# Microcontroller.net
KiCad netlist of a schematic drawn in Altium Designer
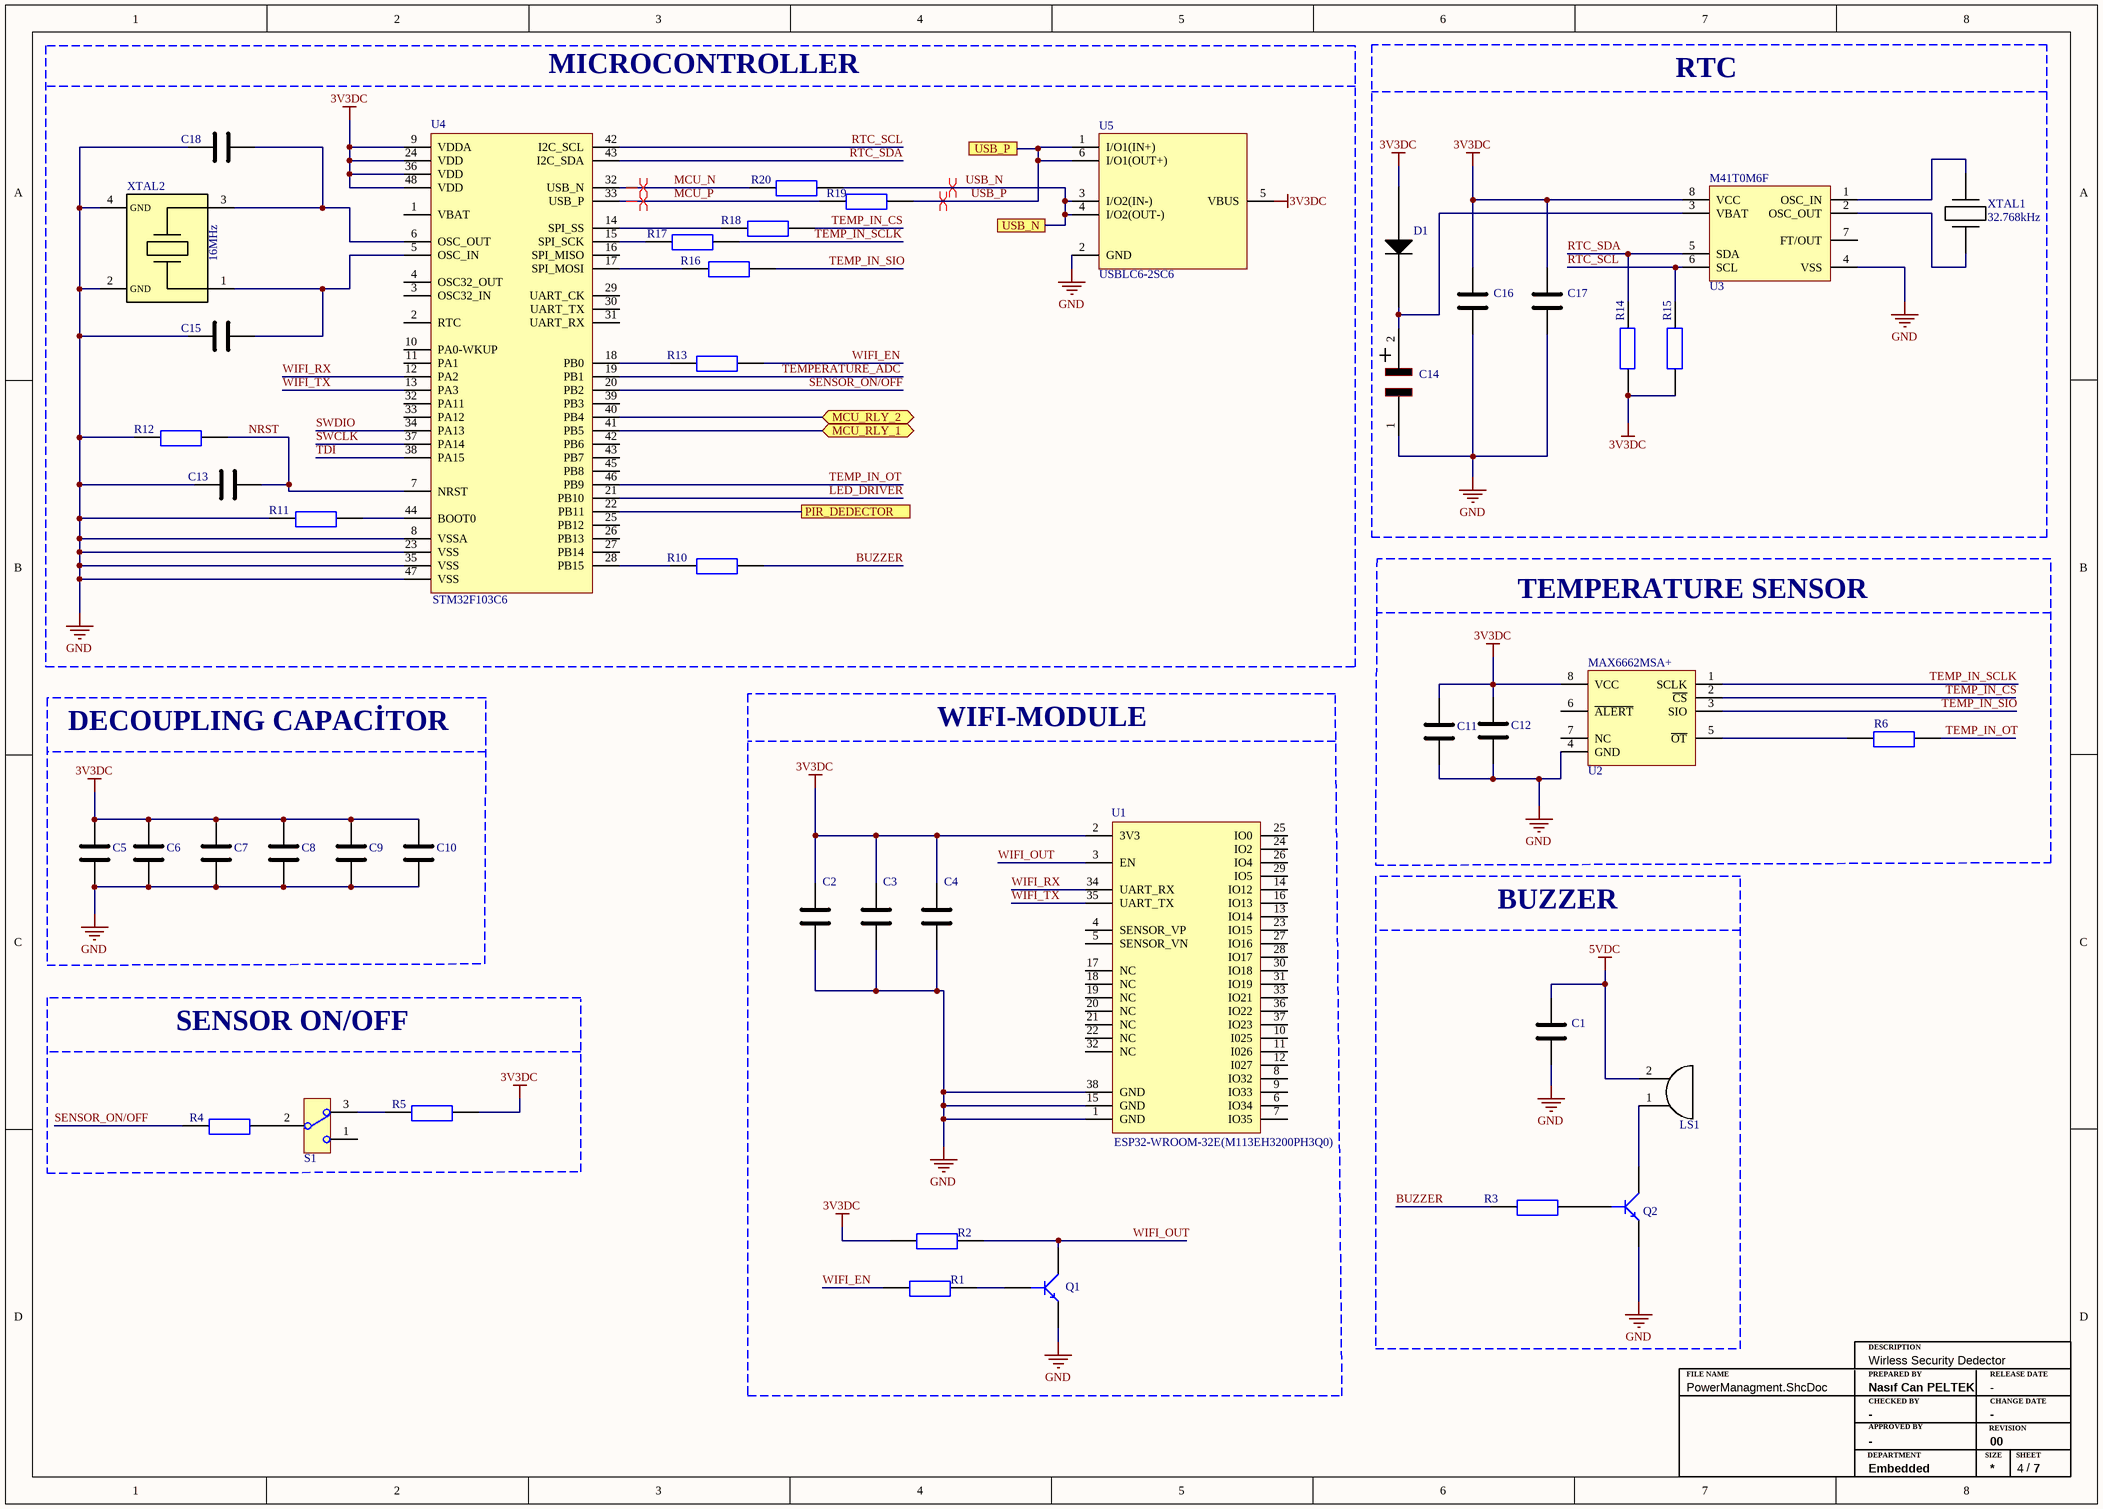
[diagram p0: Microcontroller.SchDoc]

(export (version "E")
  (design (tool "Eeschema 10.0.6"))
  (components
    (comp (ref "C1")
      (value "C0603C104K5RAC7867")
      (footprint "CAP_603")
      (description "CAP CER 100nF 50V 10% SMD 0603")
      (fields
        (field (name "MANUFACTURER") "KEMET")
        (field (name "MANUFACTURER PART NUMBER") "C0603C104K5RACTU")
        (field (name "DESIGNED BY") "Nasıf Can Peltek")
      )
      (libsource (lib "OV_00_Library") (part "CAP CER 100nF 0603"))
    )
    (comp (ref "C2")
      (value "CL21A475KAQNNNE")
      (footprint "CAP_805")
      (description "CAP CER 4.7UF 25V 10% 0805")
      (fields
        (field (name "MANUFACTURER") "Samsung")
        (field (name "TOLERANCE") "10%")
        (field (name "DESIGNED BY") "Nasıf Can Peltek")
      )
      (libsource (lib "OV_00_Library") (part "CAP CER 4.7uF 0805"))
    )
    (comp (ref "C3")
      (value "CL21B105KBFNNNE")
      (footprint "CAP_805")
      (description "CAP CER 1UF 50V 10% 0805")
      (fields
        (field (name "MANUFACTURER") "Samsung")
        (field (name "TOLERANCE") "10%")
        (field (name "DESIGNED BY") "Nasıf Can Peltek")
      )
      (libsource (lib "OV_00_Library") (part "CAP CER 1uF 0805"))
    )
    (comp (ref "C4")
      (value "C0603C104K5RAC7867")
      (footprint "CAP_603")
      (description "CAP CER 100nF 50V 10% SMD 0603")
      (fields
        (field (name "MANUFACTURER") "KEMET")
        (field (name "MANUFACTURER PART NUMBER") "C0603C104K5RACTU")
        (field (name "DESIGNED BY") "Nasıf Can Peltek")
      )
      (libsource (lib "OV_00_Library") (part "CAP CER 100nF 0603"))
    )
    (comp (ref "C5")
      (value "CL21B105KBFNNNE")
      (footprint "CAP_805")
      (description "CAP CER 1UF 50V 10% 0805")
      (fields
        (field (name "MANUFACTURER") "Samsung")
        (field (name "TOLERANCE") "10%")
        (field (name "DESIGNED BY") "Nasıf Can Peltek")
      )
      (libsource (lib "OV_00_Library") (part "CAP CER 1uF 0805"))
    )
    (comp (ref "C6")
      (value "CL21A475KAQNNNE")
      (footprint "CAP_805")
      (description "CAP CER 4.7UF 25V 10% 0805")
      (fields
        (field (name "MANUFACTURER") "Samsung")
        (field (name "TOLERANCE") "10%")
        (field (name "DESIGNED BY") "Nasıf Can Peltek")
      )
      (libsource (lib "OV_00_Library") (part "CAP CER 4.7uF 0805"))
    )
    (comp (ref "C7")
      (value "C0603C104K5RAC7867")
      (footprint "CAP_603")
      (description "CAP CER 100nF 50V 10% SMD 0603")
      (fields
        (field (name "MANUFACTURER") "KEMET")
        (field (name "MANUFACTURER PART NUMBER") "C0603C104K5RACTU")
        (field (name "DESIGNED BY") "Nasıf Can Peltek")
      )
      (libsource (lib "OV_00_Library") (part "CAP CER 100nF 0603"))
    )
    (comp (ref "C8")
      (value "C0603C104K5RAC7867")
      (footprint "CAP_603")
      (description "CAP CER 100nF 50V 10% SMD 0603")
      (fields
        (field (name "MANUFACTURER") "KEMET")
        (field (name "MANUFACTURER PART NUMBER") "C0603C104K5RACTU")
        (field (name "DESIGNED BY") "Nasıf Can Peltek")
      )
      (libsource (lib "OV_00_Library") (part "CAP CER 100nF 0603"))
    )
    (comp (ref "C9")
      (value "C0603C104K5RAC7867")
      (footprint "CAP_603")
      (description "CAP CER 100nF 50V 10% SMD 0603")
      (fields
        (field (name "MANUFACTURER") "KEMET")
        (field (name "MANUFACTURER PART NUMBER") "C0603C104K5RACTU")
        (field (name "DESIGNED BY") "Nasıf Can Peltek")
      )
      (libsource (lib "OV_00_Library") (part "CAP CER 100nF 0603"))
    )
    (comp (ref "C10")
      (value "C0603C104K5RAC7867")
      (footprint "CAP_603")
      (description "CAP CER 100nF 50V 10% SMD 0603")
      (fields
        (field (name "MANUFACTURER") "KEMET")
        (field (name "MANUFACTURER PART NUMBER") "C0603C104K5RACTU")
        (field (name "DESIGNED BY") "Nasıf Can Peltek")
      )
      (libsource (lib "OV_00_Library") (part "CAP CER 100nF 0603"))
    )
    (comp (ref "C11")
      (value "CL21B105KBFNNNE")
      (footprint "CAP_805")
      (description "CAP CER 1UF 50V 10% 0805")
      (fields
        (field (name "MANUFACTURER") "Samsung")
        (field (name "TOLERANCE") "10%")
        (field (name "DESIGNED BY") "Nasıf Can Peltek")
      )
      (libsource (lib "OV_00_Library") (part "CAP CER 1uF 0805"))
    )
    (comp (ref "C12")
      (value "C0603C104K5RAC7867")
      (footprint "CAP_603")
      (description "CAP CER 100nF 50V 10% SMD 0603")
      (fields
        (field (name "MANUFACTURER") "KEMET")
        (field (name "MANUFACTURER PART NUMBER") "C0603C104K5RACTU")
        (field (name "DESIGNED BY") "Nasıf Can Peltek")
      )
      (libsource (lib "OV_00_Library") (part "CAP CER 100nF 0603"))
    )
    (comp (ref "C13")
      (value "C0603C104K5RAC7867")
      (footprint "CAP_603")
      (description "CAP CER 100nF 50V 10% SMD 0603")
      (fields
        (field (name "MANUFACTURER") "KEMET")
        (field (name "MANUFACTURER PART NUMBER") "C0603C104K5RACTU")
        (field (name "DESIGNED BY") "Nasıf Can Peltek")
      )
      (libsource (lib "OV_00_Library") (part "CAP CER 100nF 0603"))
    )
    (comp (ref "C14")
      (value "ESH477M050AH4AA")
      (footprint "CAP_RADIAL_D10_P5")
      (description "Aluminum Electrolytic Capacitors Radial, Can  470 µF 50 V 2000 Hrs @ 105°C")
      (fields
        (field (name "MANUFACTURER") "KEMET")
        (field (name "TOLERANCE") "20%")
        (field (name "DESIGNED BY") "Nasıf Can Peltek")
      )
      (libsource (lib "OV_00_Library") (part "CAP ALU 470uF"))
    )
    (comp (ref "C15")
      (value "CL10C200JB8NNNC")
      (footprint "CAP_603")
      (description "CAP CER 20PF 50V 5% SMD 0603")
      (fields
        (field (name "MANUFACTURER") "Samsung")
        (field (name "TOLERANCE") "5%")
        (field (name "DESIGNED BY") "Nasıf Can Peltek")
      )
      (libsource (lib "OV_00_Library") (part "CAP CER 20pF 0603"))
    )
    (comp (ref "C16")
      (value "CL21B104KBCNNNC")
      (footprint "CAP_805")
      (description "CAP CER 0.1UF 50V 10%0805")
      (fields
        (field (name "MANUFACTURER") "Samsung")
        (field (name "TOLERANCE") "10%")
        (field (name "DESIGNED BY") "Nasıf Can Peltek")
      )
      (libsource (lib "OV_00_Library") (part "CAP CER 100nF 0805"))
    )
    (comp (ref "C17")
      (value "CL21B105KBFNNNE")
      (footprint "CAP_805")
      (description "CAP CER 1UF 50V 10% 0805")
      (fields
        (field (name "MANUFACTURER") "Samsung")
        (field (name "TOLERANCE") "10%")
        (field (name "DESIGNED BY") "Nasıf Can Peltek")
      )
      (libsource (lib "OV_00_Library") (part "CAP CER 1uF 0805"))
    )
    (comp (ref "C18")
      (value "CL10C200JB8NNNC")
      (footprint "CAP_603")
      (description "CAP CER 20PF 50V 5% SMD 0603")
      (fields
        (field (name "MANUFACTURER") "Samsung")
        (field (name "TOLERANCE") "5%")
        (field (name "DESIGNED BY") "Nasıf Can Peltek")
      )
      (libsource (lib "OV_00_Library") (part "CAP CER 20pF 0603"))
    )
    (comp (ref "D1")
      (value "1N4148WS")
      (footprint "SOD-323F")
      (description "Diode 75 V 150mA Surface Mount SOD-323F")
      (fields
        (field (name "MANUFACTURER") "ON Semiconductor / Fairchild")
        (field (name "DESIGNED BY") "Nasıf Can Peltek")
      )
      (libsource (lib "OV_00_Library") (part "1N4148WS"))
    )
    (comp (ref "LS1")
      (value "CMI-1275C-050")
      (footprint "CMI-1275C-050")
      (description "Buzzer 12 mm, 5 Vdc, 90 dB, 3.1 kHz, Through Hole, Magnetic Audio Indicator Buzzer")
      (fields (field (name "MANUFACTURER") "CUI") (field (name "DESIGNED BY") "Nasıf Can Peltek"))
      (libsource (lib "OV_00_Library") (part "CMI-1275C-050"))
    )
    (comp (ref "Q1")
      (value "MMBT3904-7-F")
      (footprint "SOT_23_3")
      (description "NPN Ic=200mA Vceo=40V hfe=100~300 fT=310MHz P=300mW SOT-23")
      (fields (field (name "MANUFACTURER") "Diodes Zetex") (field (name "DESIGNED BY") "Nasıf Can Peltek"))
      (libsource (lib "OV_00_Library") (part "MMBT3904-7-F"))
    )
    (comp (ref "Q2")
      (value "MMBT3904-7-F")
      (footprint "SOT_23_3")
      (description "NPN Ic=200mA Vceo=40V hfe=100~300 fT=310MHz P=300mW SOT-23")
      (fields (field (name "MANUFACTURER") "Diodes Zetex") (field (name "DESIGNED BY") "Nasıf Can Peltek"))
      (libsource (lib "OV_00_Library") (part "MMBT3904-7-F"))
    )
    (comp (ref "R1")
      (value "RC0603JR-07200RL")
      (footprint "RES_603")
      (description "RES SMD 220Ohm OHM 5% 0603 SMD")
      (fields
        (field (name "MANUFACTURER") "Yageo")
        (field (name "TOLERANCE") "5%")
        (field (name "DESIGNED BY") "Nasıf Can Peltek")
      )
      (libsource (lib "OV_00_Library") (part "RES 200 Ohm 0603"))
    )
    (comp (ref "R2")
      (value "RC0603FR-071KL")
      (footprint "RES_603")
      (description "RES SMD 1K OHM 1%  0603 SMD")
      (fields
        (field (name "MANUFACTURER") "Yageo")
        (field (name "TOLERANCE") "1%")
        (field (name "DESIGNED BY") "Nasıf Can Peltek")
      )
      (libsource (lib "OV_00_Library") (part "RES 1K 0603"))
    )
    (comp (ref "R3")
      (value "RC0603JR-07200RL")
      (footprint "RES_603")
      (description "RES SMD 220Ohm OHM 5% 0603 SMD")
      (fields
        (field (name "MANUFACTURER") "Yageo")
        (field (name "TOLERANCE") "5%")
        (field (name "DESIGNED BY") "Nasıf Can Peltek")
      )
      (libsource (lib "OV_00_Library") (part "RES 200 Ohm 0603"))
    )
    (comp (ref "R4")
      (value "RC0603JR-070RL")
      (footprint "RES_603")
      (description "RES SMD 0 OHM JUMPER 1/10W 0603")
      (fields
        (field (name "MANUFACTURER") "Yageo")
        (field (name "TOLERANCE") "1%")
        (field (name "DESIGNED BY") "Nasıf Can Peltek")
      )
      (libsource (lib "OV_00_Library") (part "RES 0R 0603"))
    )
    (comp (ref "R5")
      (value "RC0603JR-070RL")
      (footprint "RES_603")
      (description "RES SMD 0 OHM JUMPER 1/10W 0603")
      (fields
        (field (name "MANUFACTURER") "Yageo")
        (field (name "TOLERANCE") "1%")
        (field (name "DESIGNED BY") "Nasıf Can Peltek")
      )
      (libsource (lib "OV_00_Library") (part "RES 0R 0603"))
    )
    (comp (ref "R6")
      (value "RC0603JR-07200RL")
      (footprint "RES_603")
      (description "RES SMD 220Ohm OHM 5% 0603 SMD")
      (fields
        (field (name "MANUFACTURER") "Yageo")
        (field (name "TOLERANCE") "5%")
        (field (name "DESIGNED BY") "Nasıf Can Peltek")
      )
      (libsource (lib "OV_00_Library") (part "RES 200 Ohm 0603"))
    )
    (comp (ref "R10")
      (value "RC0603JR-07200RL")
      (footprint "RES_603")
      (description "RES SMD 220Ohm OHM 5% 0603 SMD")
      (fields
        (field (name "MANUFACTURER") "Yageo")
        (field (name "TOLERANCE") "5%")
        (field (name "DESIGNED BY") "Nasıf Can Peltek")
      )
      (libsource (lib "OV_00_Library") (part "RES 200 Ohm 0603"))
    )
    (comp (ref "R11")
      (value "RC0603JR-07200RL")
      (footprint "RES_603")
      (description "RES SMD 220Ohm OHM 5% 0603 SMD")
      (fields
        (field (name "MANUFACTURER") "Yageo")
        (field (name "TOLERANCE") "5%")
        (field (name "DESIGNED BY") "Nasıf Can Peltek")
      )
      (libsource (lib "OV_00_Library") (part "RES 200 Ohm 0603"))
    )
    (comp (ref "R12")
      (value "RC0603JR-07200RL")
      (footprint "RES_603")
      (description "RES SMD 220Ohm OHM 5% 0603 SMD")
      (fields
        (field (name "MANUFACTURER") "Yageo")
        (field (name "TOLERANCE") "5%")
        (field (name "DESIGNED BY") "Nasıf Can Peltek")
      )
      (libsource (lib "OV_00_Library") (part "RES 200 Ohm 0603"))
    )
    (comp (ref "R13")
      (value "RC0603JR-07200RL")
      (footprint "RES_603")
      (description "RES SMD 220Ohm OHM 5% 0603 SMD")
      (fields
        (field (name "MANUFACTURER") "Yageo")
        (field (name "TOLERANCE") "5%")
        (field (name "DESIGNED BY") "Nasıf Can Peltek")
      )
      (libsource (lib "OV_00_Library") (part "RES 200 Ohm 0603"))
    )
    (comp (ref "R14")
      (value "RC0603JR-074K7L")
      (footprint "RES_603")
      (description "RES SMD 4.7K OHM 5%  0603 SMD")
      (fields
        (field (name "MANUFACTURER") "Yageo")
        (field (name "TOLERANCE") "5%")
        (field (name "DESIGNED BY") "Nasıf Can Peltek")
      )
      (libsource (lib "OV_00_Library") (part "RES 4K7 0603"))
    )
    (comp (ref "R15")
      (value "RC0603JR-074K7L")
      (footprint "RES_603")
      (description "RES SMD 4.7K OHM 5%  0603 SMD")
      (fields
        (field (name "MANUFACTURER") "Yageo")
        (field (name "TOLERANCE") "5%")
        (field (name "DESIGNED BY") "Nasıf Can Peltek")
      )
      (libsource (lib "OV_00_Library") (part "RES 4K7 0603"))
    )
    (comp (ref "R16")
      (value "RC0603JR-07200RL")
      (footprint "RES_603")
      (description "RES SMD 220Ohm OHM 5% 0603 SMD")
      (fields
        (field (name "MANUFACTURER") "Yageo")
        (field (name "TOLERANCE") "5%")
        (field (name "DESIGNED BY") "Nasıf Can Peltek")
      )
      (libsource (lib "OV_00_Library") (part "RES 200 Ohm 0603"))
    )
    (comp (ref "R17")
      (value "RC0603JR-07200RL")
      (footprint "RES_603")
      (description "RES SMD 220Ohm OHM 5% 0603 SMD")
      (fields
        (field (name "MANUFACTURER") "Yageo")
        (field (name "TOLERANCE") "5%")
        (field (name "DESIGNED BY") "Nasıf Can Peltek")
      )
      (libsource (lib "OV_00_Library") (part "RES 200 Ohm 0603"))
    )
    (comp (ref "R18")
      (value "RC0603JR-07200RL")
      (footprint "RES_603")
      (description "RES SMD 220Ohm OHM 5% 0603 SMD")
      (fields
        (field (name "MANUFACTURER") "Yageo")
        (field (name "TOLERANCE") "5%")
        (field (name "DESIGNED BY") "Nasıf Can Peltek")
      )
      (libsource (lib "OV_00_Library") (part "RES 200 Ohm 0603"))
    )
    (comp (ref "R19")
      (value "RC0603JR-0715RL")
      (footprint "RES_603")
      (description "RES SMD 15R OHM 5% 0603 SMD")
      (fields
        (field (name "MANUFACTURER") "Yageo")
        (field (name "TOLERANCE") "5%")
        (field (name "DESIGNED BY") "Nasıf Can Peltek")
      )
      (libsource (lib "OV_00_Library") (part "RES 15R 0603"))
    )
    (comp (ref "R20")
      (value "RC0603JR-0715RL")
      (footprint "RES_603")
      (description "RES SMD 15R OHM 5% 0603 SMD")
      (fields
        (field (name "MANUFACTURER") "Yageo")
        (field (name "TOLERANCE") "5%")
        (field (name "DESIGNED BY") "Nasıf Can Peltek")
      )
      (libsource (lib "OV_00_Library") (part "RES 15R 0603"))
    )
    (comp (ref "S1")
      (value "EG1215AA")
      (footprint "EG1215AA")
      (description "Slide Switch, SPDT, 0.025A, 24V, SMD")
      (fields
        (field (name "MANUFACTURER") "E-Switch")
        (field (name "TOLERANCE") "4.95%")
        (field (name "DESIGNED BY") "Nasıf Can Peltek")
      )
      (libsource (lib "OV_00_Library") (part "EG1215AA"))
    )
    (comp (ref "U1")
      (value "ESP32-WROOM-32E")
      (footprint "ESP32-32E")
      (description "Rx Txrx Mod Wifi Trace Ant SMD")
      (fields
        (field (name "MANUFACTURER") "Espressif Systems")
        (field (name "MANUFACTURER PART NUMBER") "ESP32-WROOM-32E(M113EH3200PH3Q0)")
        (field (name "DESIGNED BY") "Nasıf Can Peltek")
      )
      (libsource (lib "OV_00_Library") (part "ESP32-WROOM-32E"))
    )
    (comp (ref "U2")
      (value "MAX6662MSA+")
      (footprint "SOIC_8")
      (description "Temp Sensor Digital Serial (3-Wire, SPI) 8-Pin SOIC N Tube")
      (fields
        (field (name "MANUFACTURER") "Maxim")
        (field (name "MANUFACTURER PART NUMBER") "MAX6662MSA+")
        (field (name "DESIGNED BY") "Nasıf Can Peltek")
      )
      (libsource (lib "OV_00_Library") (part "MAX6662MSA+"))
    )
    (comp (ref "U3")
      (value "M41T00M6F")
      (footprint "SOIC_8")
      (description "RTC M41T0 Series 2 to 5.5 V Serial I2C Real Time Clock Surface Mount - SOIC-8")
      (fields
        (field (name "MANUFACTURER") "STMicroelectronics")
        (field (name "MANUFACTURER PART NUMBER") "M41T0M6F")
        (field (name "DESIGNED BY") "Nasıf Can Peltek")
      )
      (libsource (lib "OV_00_Library") (part "M41T00M6F"))
    )
    (comp (ref "U4")
      (value "STM32F103C6T6A")
      (footprint "LQFP-48")
      (description "MCU 32-bit STM32F ARM Cortex M3 RISC 32KB Flash 2.5V/3.3V 48-Pin LQFP Tray")
      (fields
        (field (name "MANUFACTURER") "STMicroelectronics")
        (field (name "SERIES") "STM32F103C6")
        (field (name "DESIGNED BY") "Nasıf Can Peltek")
      )
      (libsource (lib "OV_00_Library") (part "STM32F103C6T6A"))
    )
    (comp (ref "U5")
      (value "USBLC6-2SC6")
      (footprint "SOT-23-6")
      (description "TVS DIODE 5.25VWM 17VC SOT23-6")
      (fields
        (field (name "MANUFACTURER") "STMicroelectronics")
        (field (name "MANUFACTURER PART NUMBER") "USBLC6-2SC6")
        (field (name "DESIGNED BY") "Nasıf Can Peltek")
      )
      (libsource (lib "OV_00_Library") (part "USB PROTECTION"))
    )
    (comp (ref "XTAL1")
      (value "ABS05-32.768KHZ-T")
      (footprint "ABS05")
      (description "Crystal 0.032768MHz ±20ppm (Tol) 12.5pF Flexural 90000Ohm 2-Pin CSMD T/R")
      (fields
        (field (name "MANUFACTURER") "Abracon")
        (field (name "TOLERANCE") "20ppm")
        (field (name "FREQUENCY") "32.768kHz")
        (field (name "DESIGNED BY") "Nasıf Can Peltek")
      )
      (libsource (lib "OV_00_Library") (part "CRYSTAL 32768KHZ"))
    )
    (comp (ref "XTAL2")
      (value "ECS-160-20-30B-TR")
      (footprint "ECS")
      (description "Crystal 16MHz ±30ppm (Tol) ±50ppm (Stability) 20pF FUND 50Ohm 4-Pin Mini-SMD T/R")
      (fields
        (field (name "MANUFACTURER") "ECS International")
        (field (name "TOLERANCE") "50ppm")
        (field (name "FREQUENCY") "16MHz")
        (field (name "DESIGNED BY") "Nasıf Can Peltek")
      )
      (libsource (lib "OV_00_Library") (part "CRYSTAL 16MHZ"))
    )
  )
  (nets
    (net (code "2") (name "/BUZZER") (class "Default")
      (node (ref "R10") (pin "2") (pinfunction "2_2") (pintype "passive"))
      (node (ref "R3") (pin "1") (pinfunction "1_1") (pintype "passive"))
    )
    (net (code "3") (name "/LED_DRIVER") (class "Default")
      (node (ref "U4") (pin "21") (pinfunction "PB10_21") (pintype "passive"))
    )
    (net (code "4") (name "/MCU_N") (class "Default")
      (node (ref "R20") (pin "1") (pinfunction "1_1") (pintype "passive"))
      (node (ref "U4") (pin "32") (pinfunction "USB_N_32") (pintype "passive"))
    )
    (net (code "5") (name "/MCU_P") (class "Default")
      (node (ref "R19") (pin "1") (pinfunction "1_1") (pintype "passive"))
      (node (ref "U4") (pin "33") (pinfunction "USB_P_33") (pintype "passive"))
    )
    (net (code "6") (name "/MCU_RLY_1") (class "Default")
      (node (ref "U4") (pin "41") (pinfunction "PB5_41") (pintype "passive"))
    )
    (net (code "7") (name "/MCU_RLY_2") (class "Default")
      (node (ref "U4") (pin "40") (pinfunction "PB4_40") (pintype "passive"))
    )
    (net (code "8") (name "/NRST") (class "Default")
      (node (ref "C13") (pin "2") (pinfunction "2_2") (pintype "passive"))
      (node (ref "R12") (pin "2") (pinfunction "2_2") (pintype "passive"))
      (node (ref "U4") (pin "7") (pinfunction "NRST_7") (pintype "passive"))
    )
    (net (code "9") (name "/PIR_DEDECTOR") (class "Default")
      (node (ref "U4") (pin "22") (pinfunction "PB11_22") (pintype "passive"))
    )
    (net (code "10") (name "/RTC_SCL") (class "Default")
      (node (ref "R15") (pin "1") (pinfunction "1_1") (pintype "passive"))
      (node (ref "U3") (pin "6") (pinfunction "SCL_6") (pintype "passive"))
      (node (ref "U4") (pin "42") (pinfunction "I2C_SCL_42") (pintype "passive"))
    )
    (net (code "11") (name "/RTC_SDA") (class "Default")
      (node (ref "R14") (pin "1") (pinfunction "1_1") (pintype "passive"))
      (node (ref "U3") (pin "5") (pinfunction "SDA_5") (pintype "passive"))
      (node (ref "U4") (pin "43") (pinfunction "I2C_SDA_43") (pintype "passive"))
    )
    (net (code "12") (name "/SENSOR_ON{slash}OFF") (class "Default")
      (node (ref "R4") (pin "1") (pinfunction "1_1") (pintype "passive"))
      (node (ref "U4") (pin "20") (pinfunction "PB2_20") (pintype "passive"))
    )
    (net (code "13") (name "/SWCLK") (class "Default")
      (node (ref "U4") (pin "37") (pinfunction "PA14_37") (pintype "passive"))
    )
    (net (code "14") (name "/SWDIO") (class "Default")
      (node (ref "U4") (pin "34") (pinfunction "PA13_34") (pintype "passive"))
    )
    (net (code "15") (name "/TDI") (class "Default")
      (node (ref "U4") (pin "38") (pinfunction "PA15_38") (pintype "passive"))
    )
    (net (code "16") (name "/TEMPERATURE_ADC") (class "Default")
      (node (ref "U4") (pin "19") (pinfunction "PB1_19") (pintype "passive"))
    )
    (net (code "17") (name "/TEMP_IN_CS") (class "Default")
      (node (ref "R18") (pin "2") (pinfunction "2_2") (pintype "passive"))
      (node (ref "U2") (pin "2") (pinfunction "~{CS}_2") (pintype "passive"))
    )
    (net (code "18") (name "/TEMP_IN_OT") (class "Default")
      (node (ref "R6") (pin "2") (pinfunction "2_2") (pintype "passive"))
      (node (ref "U4") (pin "46") (pinfunction "PB9_46") (pintype "passive"))
    )
    (net (code "19") (name "/TEMP_IN_SCLK") (class "Default")
      (node (ref "R17") (pin "2") (pinfunction "2_2") (pintype "passive"))
      (node (ref "U2") (pin "1") (pinfunction "SCLK_1") (pintype "passive"))
    )
    (net (code "20") (name "/TEMP_IN_SIO") (class "Default")
      (node (ref "R16") (pin "2") (pinfunction "2_2") (pintype "passive"))
      (node (ref "U2") (pin "3") (pinfunction "SIO_3") (pintype "passive"))
    )
    (net (code "21") (name "/USB_N") (class "Default")
      (node (ref "R20") (pin "2") (pinfunction "2_2") (pintype "passive"))
      (node (ref "U5") (pin "3") (pinfunction "I/O2(IN-)_3") (pintype "passive"))
      (node (ref "U5") (pin "4") (pinfunction "I/O2(OUT-)_4") (pintype "passive"))
    )
    (net (code "22") (name "/USB_P") (class "Default")
      (node (ref "R19") (pin "2") (pinfunction "2_2") (pintype "passive"))
      (node (ref "U5") (pin "1") (pinfunction "I/O1(IN+)_1") (pintype "passive"))
      (node (ref "U5") (pin "6") (pinfunction "I/O1(OUT+)_6") (pintype "passive"))
    )
    (net (code "23") (name "/WIFI_EN") (class "Default")
      (node (ref "R1") (pin "1") (pinfunction "1_1") (pintype "passive"))
      (node (ref "R13") (pin "2") (pinfunction "2_2") (pintype "passive"))
    )
    (net (code "24") (name "/WIFI_OUT") (class "Default")
      (node (ref "Q1") (pin "3") (pinfunction "C_3") (pintype "passive"))
      (node (ref "R2") (pin "2") (pinfunction "2_2") (pintype "passive"))
      (node (ref "U1") (pin "3") (pinfunction "EN_3") (pintype "passive"))
    )
    (net (code "25") (name "/WIFI_RX") (class "Default")
      (node (ref "U1") (pin "34") (pinfunction "UART_RX_34") (pintype "passive"))
      (node (ref "U4") (pin "12") (pinfunction "PA2_12") (pintype "passive"))
    )
    (net (code "26") (name "/WIFI_TX") (class "Default")
      (node (ref "U1") (pin "35") (pinfunction "UART_TX_35") (pintype "passive"))
      (node (ref "U4") (pin "13") (pinfunction "PA3_13") (pintype "passive"))
    )
    (net (code "27") (name "3V3DC") (class "Default")
      (node (ref "C10") (pin "2") (pinfunction "2_2") (pintype "passive"))
      (node (ref "C11") (pin "2") (pinfunction "2_2") (pintype "passive"))
      (node (ref "C12") (pin "2") (pinfunction "2_2") (pintype "passive"))
      (node (ref "C16") (pin "2") (pinfunction "2_2") (pintype "passive"))
      (node (ref "C17") (pin "2") (pinfunction "2_2") (pintype "passive"))
      (node (ref "C2") (pin "2") (pinfunction "2_2") (pintype "passive"))
      (node (ref "C3") (pin "2") (pinfunction "2_2") (pintype "passive"))
      (node (ref "C4") (pin "2") (pinfunction "2_2") (pintype "passive"))
      (node (ref "C5") (pin "2") (pinfunction "2_2") (pintype "passive"))
      (node (ref "C6") (pin "2") (pinfunction "2_2") (pintype "passive"))
      (node (ref "C7") (pin "2") (pinfunction "2_2") (pintype "passive"))
      (node (ref "C8") (pin "2") (pinfunction "2_2") (pintype "passive"))
      (node (ref "C9") (pin "2") (pinfunction "2_2") (pintype "passive"))
      (node (ref "D1") (pin "1") (pinfunction "+_1") (pintype "passive"))
      (node (ref "R14") (pin "2") (pinfunction "2_2") (pintype "passive"))
      (node (ref "R15") (pin "2") (pinfunction "2_2") (pintype "passive"))
      (node (ref "R2") (pin "1") (pinfunction "1_1") (pintype "passive"))
      (node (ref "R5") (pin "2") (pinfunction "2_2") (pintype "passive"))
      (node (ref "U1") (pin "2") (pinfunction "3V3_2") (pintype "passive"))
      (node (ref "U2") (pin "8") (pinfunction "VCC_8") (pintype "passive"))
      (node (ref "U3") (pin "8") (pinfunction "VCC_8") (pintype "passive"))
      (node (ref "U4") (pin "24") (pinfunction "VDD_24") (pintype "passive"))
      (node (ref "U4") (pin "36") (pinfunction "VDD_36") (pintype "passive"))
      (node (ref "U4") (pin "48") (pinfunction "VDD_48") (pintype "passive"))
      (node (ref "U4") (pin "9") (pinfunction "VDDA_9") (pintype "passive"))
      (node (ref "U5") (pin "5") (pinfunction "VBUS_5") (pintype "passive"))
    )
    (net (code "28") (name "5VDC") (class "Default")
      (node (ref "C1") (pin "2") (pinfunction "2_2") (pintype "passive"))
      (node (ref "LS1") (pin "2") (pinfunction "-_2") (pintype "passive"))
    )
    (net (code "29") (name "GND") (class "Default")
      (node (ref "C1") (pin "1") (pinfunction "1_1") (pintype "passive"))
      (node (ref "C10") (pin "1") (pinfunction "1_1") (pintype "passive"))
      (node (ref "C11") (pin "1") (pinfunction "1_1") (pintype "passive"))
      (node (ref "C12") (pin "1") (pinfunction "1_1") (pintype "passive"))
      (node (ref "C13") (pin "1") (pinfunction "1_1") (pintype "passive"))
      (node (ref "C14") (pin "1") (pinfunction "CATHODE(-)_1") (pintype "passive"))
      (node (ref "C15") (pin "2") (pinfunction "2_2") (pintype "passive"))
      (node (ref "C16") (pin "1") (pinfunction "1_1") (pintype "passive"))
      (node (ref "C17") (pin "1") (pinfunction "1_1") (pintype "passive"))
      (node (ref "C18") (pin "1") (pinfunction "1_1") (pintype "passive"))
      (node (ref "C2") (pin "1") (pinfunction "1_1") (pintype "passive"))
      (node (ref "C3") (pin "1") (pinfunction "1_1") (pintype "passive"))
      (node (ref "C4") (pin "1") (pinfunction "1_1") (pintype "passive"))
      (node (ref "C5") (pin "1") (pinfunction "1_1") (pintype "passive"))
      (node (ref "C6") (pin "1") (pinfunction "1_1") (pintype "passive"))
      (node (ref "C7") (pin "1") (pinfunction "1_1") (pintype "passive"))
      (node (ref "C8") (pin "1") (pinfunction "1_1") (pintype "passive"))
      (node (ref "C9") (pin "1") (pinfunction "1_1") (pintype "passive"))
      (node (ref "Q1") (pin "2") (pinfunction "E_2") (pintype "passive"))
      (node (ref "Q2") (pin "2") (pinfunction "E_2") (pintype "passive"))
      (node (ref "R11") (pin "1") (pinfunction "1_1") (pintype "passive"))
      (node (ref "R12") (pin "1") (pinfunction "1_1") (pintype "passive"))
      (node (ref "U1") (pin "1") (pinfunction "GND_1") (pintype "passive"))
      (node (ref "U1") (pin "15") (pinfunction "GND_15") (pintype "passive"))
      (node (ref "U1") (pin "38") (pinfunction "GND_38") (pintype "passive"))
      (node (ref "U2") (pin "4") (pinfunction "GND_4") (pintype "passive"))
      (node (ref "U3") (pin "4") (pinfunction "VSS_4") (pintype "passive"))
      (node (ref "U4") (pin "23") (pinfunction "VSS_23") (pintype "passive"))
      (node (ref "U4") (pin "35") (pinfunction "VSS_35") (pintype "passive"))
      (node (ref "U4") (pin "47") (pinfunction "VSS_47") (pintype "passive"))
      (node (ref "U4") (pin "8") (pinfunction "VSSA_8") (pintype "passive"))
      (node (ref "U5") (pin "2") (pinfunction "GND_2") (pintype "passive"))
      (node (ref "XTAL2") (pin "2") (pinfunction "GND_2") (pintype "passive"))
      (node (ref "XTAL2") (pin "4") (pinfunction "GND_4") (pintype "passive"))
    )
    (net (code "30") (name "Net-(C14-ANODE(+))") (class "Default")
      (node (ref "C14") (pin "2") (pinfunction "ANODE(+)_2") (pintype "passive"))
      (node (ref "D1") (pin "2") (pinfunction "-_2") (pintype "passive"))
      (node (ref "U3") (pin "3") (pinfunction "VBAT_3") (pintype "passive"))
    )
    (net (code "31") (name "Net-(Q1-B)") (class "Default")
      (node (ref "Q1") (pin "1") (pinfunction "B_1") (pintype "passive"))
      (node (ref "R1") (pin "2") (pinfunction "2_2") (pintype "passive"))
    )
    (net (code "32") (name "Net-(Q2-B)") (class "Default")
      (node (ref "Q2") (pin "1") (pinfunction "B_1") (pintype "passive"))
      (node (ref "R3") (pin "2") (pinfunction "2_2") (pintype "passive"))
    )
    (net (code "33") (name "Net-(Q2-C)") (class "Default")
      (node (ref "LS1") (pin "1") (pinfunction "-_1") (pintype "passive"))
      (node (ref "Q2") (pin "3") (pinfunction "C_3") (pintype "passive"))
    )
    (net (code "34") (name "Net-(R4-Pad2)") (class "Default")
      (node (ref "R4") (pin "2") (pinfunction "2_2") (pintype "passive"))
      (node (ref "S1") (pin "2") (pinfunction "2_2") (pintype "passive"))
    )
    (net (code "35") (name "Net-(R5-Pad1)") (class "Default")
      (node (ref "R5") (pin "1") (pinfunction "1_1") (pintype "passive"))
      (node (ref "S1") (pin "3") (pinfunction "3_3") (pintype "passive"))
    )
    (net (code "36") (name "Net-(U2-~{OT})") (class "Default")
      (node (ref "R6") (pin "1") (pinfunction "1_1") (pintype "passive"))
      (node (ref "U2") (pin "5") (pinfunction "~{OT}_5") (pintype "passive"))
    )
    (net (code "37") (name "Net-(U3-OSC_IN)") (class "Default")
      (node (ref "U3") (pin "1") (pinfunction "OSC_IN_1") (pintype "passive"))
      (node (ref "XTAL1") (pin "2") (pinfunction "2_2") (pintype "passive"))
    )
    (net (code "38") (name "Net-(U3-OSC_OUT)") (class "Default")
      (node (ref "U3") (pin "2") (pinfunction "OSC_OUT_2") (pintype "passive"))
      (node (ref "XTAL1") (pin "1") (pinfunction "1_1") (pintype "passive"))
    )
    (net (code "39") (name "Net-(U4-BOOT0)") (class "Default")
      (node (ref "R11") (pin "2") (pinfunction "2_2") (pintype "passive"))
      (node (ref "U4") (pin "44") (pinfunction "BOOT0_44") (pintype "passive"))
    )
    (net (code "40") (name "Net-(U4-OSC_IN)") (class "Default")
      (node (ref "C15") (pin "1") (pinfunction "1_1") (pintype "passive"))
      (node (ref "U4") (pin "5") (pinfunction "OSC_IN_5") (pintype "passive"))
      (node (ref "XTAL2") (pin "1") (pinfunction "1_1") (pintype "passive"))
    )
    (net (code "41") (name "Net-(U4-OSC_OUT)") (class "Default")
      (node (ref "C18") (pin "2") (pinfunction "2_2") (pintype "passive"))
      (node (ref "U4") (pin "6") (pinfunction "OSC_OUT_6") (pintype "passive"))
      (node (ref "XTAL2") (pin "3") (pinfunction "3_3") (pintype "passive"))
    )
    (net (code "42") (name "Net-(U4-PB0)") (class "Default")
      (node (ref "R13") (pin "1") (pinfunction "1_1") (pintype "passive"))
      (node (ref "U4") (pin "18") (pinfunction "PB0_18") (pintype "passive"))
    )
    (net (code "43") (name "Net-(U4-PB15)") (class "Default")
      (node (ref "R10") (pin "1") (pinfunction "1_1") (pintype "passive"))
      (node (ref "U4") (pin "28") (pinfunction "PB15_28") (pintype "passive"))
    )
    (net (code "44") (name "Net-(U4-SPI_MOSI)") (class "Default")
      (node (ref "R16") (pin "1") (pinfunction "1_1") (pintype "passive"))
      (node (ref "U4") (pin "17") (pinfunction "SPI_MOSI_17") (pintype "passive"))
    )
    (net (code "45") (name "Net-(U4-SPI_SCK)") (class "Default")
      (node (ref "R17") (pin "1") (pinfunction "1_1") (pintype "passive"))
      (node (ref "U4") (pin "15") (pinfunction "SPI_SCK_15") (pintype "passive"))
    )
    (net (code "46") (name "Net-(U4-SPI_SS)") (class "Default")
      (node (ref "R18") (pin "1") (pinfunction "1_1") (pintype "passive"))
      (node (ref "U4") (pin "14") (pinfunction "SPI_SS_14") (pintype "passive"))
    )
    (net (code "47") (name "unconnected-(S1-Pad1)") (class "Default")
      (node (ref "S1") (pin "1") (pinfunction "1_1") (pintype "passive"))
    )
    (net (code "48") (name "unconnected-(U1-I025-Pad10)") (class "Default")
      (node (ref "U1") (pin "10") (pinfunction "I025_10") (pintype "passive"))
    )
    (net (code "49") (name "unconnected-(U1-I026-Pad11)") (class "Default")
      (node (ref "U1") (pin "11") (pinfunction "I026_11") (pintype "passive"))
    )
    (net (code "50") (name "unconnected-(U1-I027-Pad12)") (class "Default")
      (node (ref "U1") (pin "12") (pinfunction "I027_12") (pintype "passive"))
    )
    (net (code "51") (name "unconnected-(U1-IO0-Pad25)") (class "Default")
      (node (ref "U1") (pin "25") (pinfunction "IO0_25") (pintype "passive"))
    )
    (net (code "52") (name "unconnected-(U1-IO2-Pad24)") (class "Default")
      (node (ref "U1") (pin "24") (pinfunction "IO2_24") (pintype "passive"))
    )
    (net (code "53") (name "unconnected-(U1-IO4-Pad26)") (class "Default")
      (node (ref "U1") (pin "26") (pinfunction "IO4_26") (pintype "passive"))
    )
    (net (code "54") (name "unconnected-(U1-IO5-Pad29)") (class "Default")
      (node (ref "U1") (pin "29") (pinfunction "IO5_29") (pintype "passive"))
    )
    (net (code "55") (name "unconnected-(U1-IO12-Pad14)") (class "Default")
      (node (ref "U1") (pin "14") (pinfunction "IO12_14") (pintype "passive"))
    )
    (net (code "56") (name "unconnected-(U1-IO13-Pad16)") (class "Default")
      (node (ref "U1") (pin "16") (pinfunction "IO13_16") (pintype "passive"))
    )
    (net (code "57") (name "unconnected-(U1-IO14-Pad13)") (class "Default")
      (node (ref "U1") (pin "13") (pinfunction "IO14_13") (pintype "passive"))
    )
    (net (code "58") (name "unconnected-(U1-IO15-Pad23)") (class "Default")
      (node (ref "U1") (pin "23") (pinfunction "IO15_23") (pintype "passive"))
    )
    (net (code "59") (name "unconnected-(U1-IO16-Pad27)") (class "Default")
      (node (ref "U1") (pin "27") (pinfunction "IO16_27") (pintype "passive"))
    )
    (net (code "60") (name "unconnected-(U1-IO17-Pad28)") (class "Default")
      (node (ref "U1") (pin "28") (pinfunction "IO17_28") (pintype "passive"))
    )
    (net (code "61") (name "unconnected-(U1-IO18-Pad30)") (class "Default")
      (node (ref "U1") (pin "30") (pinfunction "IO18_30") (pintype "passive"))
    )
    (net (code "62") (name "unconnected-(U1-IO19-Pad31)") (class "Default")
      (node (ref "U1") (pin "31") (pinfunction "IO19_31") (pintype "passive"))
    )
    (net (code "63") (name "unconnected-(U1-IO21-Pad33)") (class "Default")
      (node (ref "U1") (pin "33") (pinfunction "IO21_33") (pintype "passive"))
    )
    (net (code "64") (name "unconnected-(U1-IO22-Pad36)") (class "Default")
      (node (ref "U1") (pin "36") (pinfunction "IO22_36") (pintype "passive"))
    )
    (net (code "65") (name "unconnected-(U1-IO23-Pad37)") (class "Default")
      (node (ref "U1") (pin "37") (pinfunction "IO23_37") (pintype "passive"))
    )
    (net (code "66") (name "unconnected-(U1-IO32-Pad8)") (class "Default")
      (node (ref "U1") (pin "8") (pinfunction "IO32_8") (pintype "passive"))
    )
    (net (code "67") (name "unconnected-(U1-IO33-Pad9)") (class "Default")
      (node (ref "U1") (pin "9") (pinfunction "IO33_9") (pintype "passive"))
    )
    (net (code "68") (name "unconnected-(U1-IO34-Pad6)") (class "Default")
      (node (ref "U1") (pin "6") (pinfunction "IO34_6") (pintype "passive"))
    )
    (net (code "69") (name "unconnected-(U1-IO35-Pad7)") (class "Default")
      (node (ref "U1") (pin "7") (pinfunction "IO35_7") (pintype "passive"))
    )
    (net (code "70") (name "unconnected-(U1-NC-Pad17)") (class "Default")
      (node (ref "U1") (pin "17") (pinfunction "NC_17") (pintype "passive"))
    )
    (net (code "71") (name "unconnected-(U1-NC-Pad18)") (class "Default")
      (node (ref "U1") (pin "18") (pinfunction "NC_18") (pintype "passive"))
    )
    (net (code "72") (name "unconnected-(U1-NC-Pad19)") (class "Default")
      (node (ref "U1") (pin "19") (pinfunction "NC_19") (pintype "passive"))
    )
    (net (code "73") (name "unconnected-(U1-NC-Pad20)") (class "Default")
      (node (ref "U1") (pin "20") (pinfunction "NC_20") (pintype "passive"))
    )
    (net (code "74") (name "unconnected-(U1-NC-Pad21)") (class "Default")
      (node (ref "U1") (pin "21") (pinfunction "NC_21") (pintype "passive"))
    )
    (net (code "75") (name "unconnected-(U1-NC-Pad22)") (class "Default")
      (node (ref "U1") (pin "22") (pinfunction "NC_22") (pintype "passive"))
    )
    (net (code "76") (name "unconnected-(U1-NC-Pad32)") (class "Default")
      (node (ref "U1") (pin "32") (pinfunction "NC_32") (pintype "passive"))
    )
    (net (code "77") (name "unconnected-(U1-SENSOR_VN-Pad5)") (class "Default")
      (node (ref "U1") (pin "5") (pinfunction "SENSOR_VN_5") (pintype "passive"))
    )
    (net (code "78") (name "unconnected-(U1-SENSOR_VP-Pad4)") (class "Default")
      (node (ref "U1") (pin "4") (pinfunction "SENSOR_VP_4") (pintype "passive"))
    )
    (net (code "79") (name "unconnected-(U2-NC-Pad7)") (class "Default")
      (node (ref "U2") (pin "7") (pinfunction "NC_7") (pintype "passive"))
    )
    (net (code "80") (name "unconnected-(U2-~{ALERT}-Pad6)") (class "Default")
      (node (ref "U2") (pin "6") (pinfunction "~{ALERT}_6") (pintype "passive"))
    )
    (net (code "81") (name "unconnected-(U3-FT{slash}OUT-Pad7)") (class "Default")
      (node (ref "U3") (pin "7") (pinfunction "FT/OUT_7") (pintype "passive"))
    )
    (net (code "82") (name "unconnected-(U4-OSC32_IN-Pad3)") (class "Default")
      (node (ref "U4") (pin "3") (pinfunction "OSC32_IN_3") (pintype "passive"))
    )
    (net (code "83") (name "unconnected-(U4-OSC32_OUT-Pad4)") (class "Default")
      (node (ref "U4") (pin "4") (pinfunction "OSC32_OUT_4") (pintype "passive"))
    )
    (net (code "84") (name "unconnected-(U4-PA0-WKUP-Pad10)") (class "Default")
      (node (ref "U4") (pin "10") (pinfunction "PA0-WKUP_10") (pintype "passive"))
    )
    (net (code "85") (name "unconnected-(U4-PA1-Pad11)") (class "Default")
      (node (ref "U4") (pin "11") (pinfunction "PA1_11") (pintype "passive"))
    )
    (net (code "86") (name "unconnected-(U4-PA11-Pad32)") (class "Default")
      (node (ref "U4") (pin "32") (pinfunction "PA11_32") (pintype "passive"))
    )
    (net (code "87") (name "unconnected-(U4-PA12-Pad33)") (class "Default")
      (node (ref "U4") (pin "33") (pinfunction "PA12_33") (pintype "passive"))
    )
    (net (code "88") (name "unconnected-(U4-PB3-Pad39)") (class "Default")
      (node (ref "U4") (pin "39") (pinfunction "PB3_39") (pintype "passive"))
    )
    (net (code "89") (name "unconnected-(U4-PB6-Pad42)") (class "Default")
      (node (ref "U4") (pin "42") (pinfunction "PB6_42") (pintype "passive"))
    )
    (net (code "90") (name "unconnected-(U4-PB7-Pad43)") (class "Default")
      (node (ref "U4") (pin "43") (pinfunction "PB7_43") (pintype "passive"))
    )
    (net (code "91") (name "unconnected-(U4-PB8-Pad45)") (class "Default")
      (node (ref "U4") (pin "45") (pinfunction "PB8_45") (pintype "passive"))
    )
    (net (code "92") (name "unconnected-(U4-PB12-Pad25)") (class "Default")
      (node (ref "U4") (pin "25") (pinfunction "PB12_25") (pintype "passive"))
    )
    (net (code "93") (name "unconnected-(U4-PB13-Pad26)") (class "Default")
      (node (ref "U4") (pin "26") (pinfunction "PB13_26") (pintype "passive"))
    )
    (net (code "94") (name "unconnected-(U4-PB14-Pad27)") (class "Default")
      (node (ref "U4") (pin "27") (pinfunction "PB14_27") (pintype "passive"))
    )
    (net (code "95") (name "unconnected-(U4-RTC-Pad2)") (class "Default")
      (node (ref "U4") (pin "2") (pinfunction "RTC_2") (pintype "passive"))
    )
    (net (code "96") (name "unconnected-(U4-SPI_MISO-Pad16)") (class "Default")
      (node (ref "U4") (pin "16") (pinfunction "SPI_MISO_16") (pintype "passive"))
    )
    (net (code "97") (name "unconnected-(U4-UART_CK-Pad29)") (class "Default")
      (node (ref "U4") (pin "29") (pinfunction "UART_CK_29") (pintype "passive"))
    )
    (net (code "98") (name "unconnected-(U4-UART_RX-Pad31)") (class "Default")
      (node (ref "U4") (pin "31") (pinfunction "UART_RX_31") (pintype "passive"))
    )
    (net (code "99") (name "unconnected-(U4-UART_TX-Pad30)") (class "Default")
      (node (ref "U4") (pin "30") (pinfunction "UART_TX_30") (pintype "passive"))
    )
    (net (code "100") (name "unconnected-(U4-VBAT-Pad1)") (class "Default")
      (node (ref "U4") (pin "1") (pinfunction "VBAT_1") (pintype "passive"))
    )
  )
)
